# current_sense.net
KiCad netlist of a schematic drawn in Altium Designer
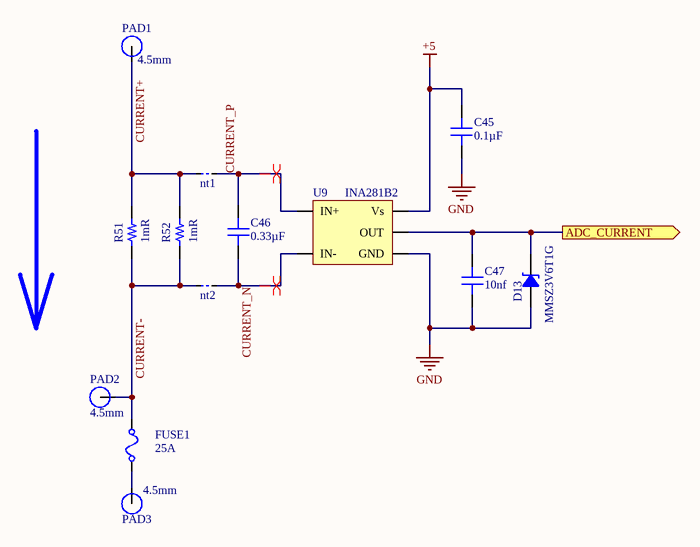
[diagram p0: current sense.SchDoc]

(export (version "E")
  (design (tool "Eeschema 10.0.6"))
  (components
    (comp (ref "C45")
      (value "0.1µF")
      (footprint "CAP 0805_2012")
      (description "CAP CER 0.1UF 100V X7R 0805")
      (fields (field (name "PART NUMBER") "AS0805KKX7R0BB104") (field (name "MANUFACTURER") "Yageo"))
      (libsource (lib "Celestial Altium Library - altium_library") (part "Capacitor"))
    )
    (comp (ref "C46")
      (value "0.33µF")
      (footprint "CAP 0805_2012")
      (description "CAP CER 0805 330NF 50V X7R 10%")
      (fields (field (name "PART NUMBER") "C0805C334K5RECAUTO") (field (name "MANUFACTURER") "KEMET"))
      (libsource (lib "Celestial Altium Library - altium_library") (part "Capacitor"))
    )
    (comp (ref "C47")
      (value "10nf")
      (footprint "CAP 0805_2012")
      (description "CAP CER 0805 10NF 100V X7R")
      (fields (field (name "PART NUMBER") "C0805X103K1RAC3316") (field (name "MANUFACTURER") "KEMET"))
      (libsource (lib "Celestial Altium Library - altium_library") (part "Capacitor"))
    )
    (comp (ref "D13")
      (value "MMSZ3V6T1G")
      (footprint "SOD-123")
      (description "DIODE ZENER 3.6V 500MW SOD123")
      (fields (field (name "MANUFACTURER") "ON Semiconductor") (field (name "TOLERANCE") "±5%"))
      (libsource (lib "Celestial Altium Library - altium_library") (part "Diode Zener"))
    )
    (comp (ref "FUSE1")
      (value "25A")
      (footprint "3522 ATOF FUSE")
      (description "3522 ATOF automotive fuse")
      (libsource (lib "My_Library_ATOF_Fuse") (part "ATOF Fuse 3522"))
    )
    (comp (ref "nt1")
      (value "NET TIE 2")
      (footprint "0.3mm")
      (libsource (lib "My_Library_Net_tie") (part "NET TIE 2"))
    )
    (comp (ref "nt2")
      (value "NET TIE 2")
      (footprint "0.3mm")
      (libsource (lib "My_Library_Net_tie") (part "NET TIE 2"))
    )
    (comp (ref "PAD1")
      (value "4.5mm")
      (footprint "Single Pad 4.5mm")
      (libsource (lib "My_Library_Single_Pad") (part "Single Pad 4.5mm"))
    )
    (comp (ref "PAD2")
      (value "4.5mm")
      (footprint "Single Pad 4.5mm")
      (libsource (lib "My_Library_Single_Pad") (part "Single Pad 4.5mm"))
    )
    (comp (ref "PAD3")
      (value "4.5mm")
      (footprint "Single Pad 4.5mm")
      (libsource (lib "My_Library_Single_Pad") (part "Single Pad 4.5mm"))
    )
    (comp (ref "R51")
      (value "1mR")
      (footprint "2512_bvt")
      (description "Res Metal Strip 2512 0.001 Ohm 1% 5W ±75ppm/°C Pad SMD Automotive T/R")
      (fields
        (field (name "MANUFACTURER") "Bourns")
        (field (name "MANUFACTURER PART NUMBER") "CSS2H-2512R-1L00FE")
      )
      (libsource (lib "My_Library_Shunt_Resistor") (part "CSS2H-2512R-1L00FE"))
    )
    (comp (ref "R52")
      (value "1mR")
      (footprint "2512_bvt")
      (description "Res Metal Strip 2512 0.001 Ohm 1% 5W ±75ppm/°C Pad SMD Automotive T/R")
      (fields
        (field (name "MANUFACTURER") "Bourns")
        (field (name "MANUFACTURER PART NUMBER") "CSS2H-2512R-1L00FE")
      )
      (libsource (lib "My_Library_Shunt_Resistor") (part "CSS2H-2512R-1L00FE"))
    )
    (comp (ref "U9")
      (value "INA281B2")
      (footprint "SOT-23(INA281)_H")
      (libsource (lib "My_Library_Current_Sense_Amplifiers") (part "INA281B2IDBVR"))
    )
  )
  (nets
    (net (code "1") (name "+5") (class "Default")
      (node (ref "C45") (pin "2") (pinfunction "2_2") (pintype "passive"))
      (node (ref "U9") (pin "3") (pinfunction "Vs_3") (pintype "passive"))
    )
    (net (code "2") (name "/ADC_CURRENT") (class "Default")
      (node (ref "C47") (pin "2") (pinfunction "2_2") (pintype "passive"))
      (node (ref "D13") (pin "2") (pinfunction "2_2") (pintype "passive"))
      (node (ref "U9") (pin "1") (pinfunction "OUT_1") (pintype "passive"))
    )
    (net (code "3") (name "/CURRENT+") (class "Default")
      (node (ref "PAD1") (pin "1") (pinfunction "1_1") (pintype "passive"))
      (node (ref "R51") (pin "2") (pinfunction "2_2") (pintype "passive"))
      (node (ref "R52") (pin "2") (pinfunction "2_2") (pintype "passive"))
      (node (ref "nt1") (pin "1") (pinfunction "1_1") (pintype "passive"))
    )
    (net (code "4") (name "/CURRENT-") (class "Default")
      (node (ref "FUSE1") (pin "2") (pinfunction "2_2") (pintype "passive"))
      (node (ref "PAD2") (pin "1") (pinfunction "1_1") (pintype "passive"))
      (node (ref "R51") (pin "1") (pinfunction "1_1") (pintype "passive"))
      (node (ref "R52") (pin "1") (pinfunction "1_1") (pintype "passive"))
      (node (ref "nt2") (pin "1") (pinfunction "1_1") (pintype "passive"))
    )
    (net (code "5") (name "/CURRENT_N") (class "Default")
      (node (ref "C46") (pin "1") (pinfunction "1_1") (pintype "passive"))
      (node (ref "U9") (pin "5") (pinfunction "IN-_5") (pintype "passive"))
      (node (ref "nt2") (pin "2") (pinfunction "2_2") (pintype "passive"))
    )
    (net (code "6") (name "/CURRENT_P") (class "Default")
      (node (ref "C46") (pin "2") (pinfunction "2_2") (pintype "passive"))
      (node (ref "U9") (pin "4") (pinfunction "IN+_4") (pintype "passive"))
      (node (ref "nt1") (pin "2") (pinfunction "2_2") (pintype "passive"))
    )
    (net (code "7") (name "GND") (class "Default")
      (node (ref "C45") (pin "1") (pinfunction "1_1") (pintype "passive"))
      (node (ref "C47") (pin "1") (pinfunction "1_1") (pintype "passive"))
      (node (ref "D13") (pin "1") (pinfunction "1_1") (pintype "passive"))
      (node (ref "U9") (pin "2") (pinfunction "GND_2") (pintype "passive"))
    )
    (net (code "8") (name "Net-(FUSE1-Pad1)") (class "Default")
      (node (ref "FUSE1") (pin "1") (pinfunction "1_1") (pintype "passive"))
      (node (ref "PAD3") (pin "1") (pinfunction "1_1") (pintype "passive"))
    )
  )
)
